# Main_DESKTOP-2772EO1_s_conflicted_copy_2.net
KiCad netlist of a schematic drawn in Altium Designer
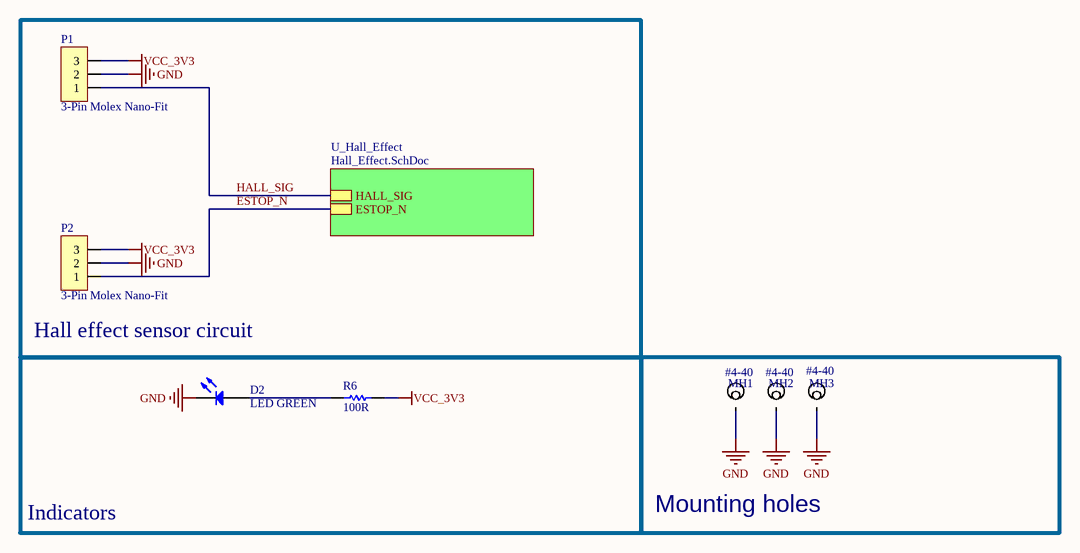
[diagram p0: Main (DESKTOP-2772EO1's conflicted copy 2019-08-13).SchDoc]

(export (version "E")
  (design (tool "Eeschema 10.0.6"))
  (components
    (comp (ref "D2")
      (value "LED GREEN")
      (footprint "LED_0805")
      (description "led")
      (fields
        (field (name "MANUFACTURER") "Lite-On Inc.")
        (field (name "MANUFACTURER PART NUMBER") "LTST-C171KGKT")
      )
      (libsource (lib "CMR_Miscellaneous_Devices") (part "LED0"))
    )
    (comp (ref "MH1")
      (value "#4-40")
      (footprint "Mounting Hole #4-40")
      (description "Mounting Hole for ANSI #4-40 w/ Flat Washer, Loose Fit")
      (libsource (lib "CMR_PCB_Components") (part "Mounting Hole #4-40, Loose Fit"))
    )
    (comp (ref "MH2")
      (value "#4-40")
      (footprint "Mounting Hole #4-40")
      (description "Mounting Hole for ANSI #4-40 w/ Flat Washer, Loose Fit")
      (libsource (lib "CMR_PCB_Components") (part "Mounting Hole #4-40, Loose Fit"))
    )
    (comp (ref "MH3")
      (value "#4-40")
      (footprint "Mounting Hole #4-40")
      (description "Mounting Hole for ANSI #4-40 w/ Flat Washer, Loose Fit")
      (libsource (lib "CMR_PCB_Components") (part "Mounting Hole #4-40, Loose Fit"))
    )
    (comp (ref "P1")
      (value "3-Pin Molex Nano-Fit")
      (footprint "MOLEX NANO-FIT 1X3")
      (description "NanoFit RA Hdr TH SR 3Ckt")
      (fields (field (name "MANUFACTURER") "Molex") (field (name "PART NUMBER") "105313-1204"))
      (libsource (lib "CMR_Connectors") (part "3-Pin Nano-Fit"))
    )
    (comp (ref "P2")
      (value "3-Pin Molex Nano-Fit")
      (footprint "MOLEX NANO-FIT 1X3")
      (description "NanoFit RA Hdr TH SR 3Ckt")
      (fields (field (name "MANUFACTURER") "Molex") (field (name "PART NUMBER") "105313-1204"))
      (libsource (lib "CMR_Connectors") (part "3-Pin Nano-Fit"))
    )
    (comp (ref "R6")
      (value "100R")
      (footprint "RESC0603(1608)_N")
      (description "100R 0.1W 5% 0603 (1608 Metric)  SMD")
      (fields (field (name "TOLERANCE") "5 %") (field (name "POWER") "0.1 W"))
      (libsource (lib "Altium Content Vault") (part "RES"))
    )
  )
  (nets
    (net (code "1") (name "/ESTOP_N") (class "Default")
      (node (ref "P2") (pin "1") (pinfunction "1_1") (pintype "passive"))
    )
    (net (code "2") (name "/HALL_SIG") (class "Default")
      (node (ref "P1") (pin "1") (pinfunction "1_1") (pintype "passive"))
    )
    (net (code "3") (name "GND") (class "Default")
      (node (ref "D2") (pin "1") (pinfunction "K_1") (pintype "passive"))
      (node (ref "MH1") (pin "0") (pinfunction "0_0") (pintype "passive"))
      (node (ref "MH2") (pin "0") (pinfunction "0_0") (pintype "passive"))
      (node (ref "MH3") (pin "0") (pinfunction "0_0") (pintype "passive"))
      (node (ref "P1") (pin "2") (pinfunction "2_2") (pintype "passive"))
      (node (ref "P2") (pin "2") (pinfunction "2_2") (pintype "passive"))
    )
    (net (code "4") (name "Net-(D2-A)") (class "Default")
      (node (ref "D2") (pin "2") (pinfunction "A_2") (pintype "passive"))
      (node (ref "R6") (pin "1") (pinfunction "1_1") (pintype "passive"))
    )
    (net (code "5") (name "VCC_3V3") (class "Default")
      (node (ref "P1") (pin "3") (pinfunction "3_3") (pintype "passive"))
      (node (ref "P2") (pin "3") (pinfunction "3_3") (pintype "passive"))
      (node (ref "R6") (pin "2") (pinfunction "2_2") (pintype "passive"))
    )
  )
)
